# Schematic.net
KiCad netlist of a schematic drawn in EAGLE
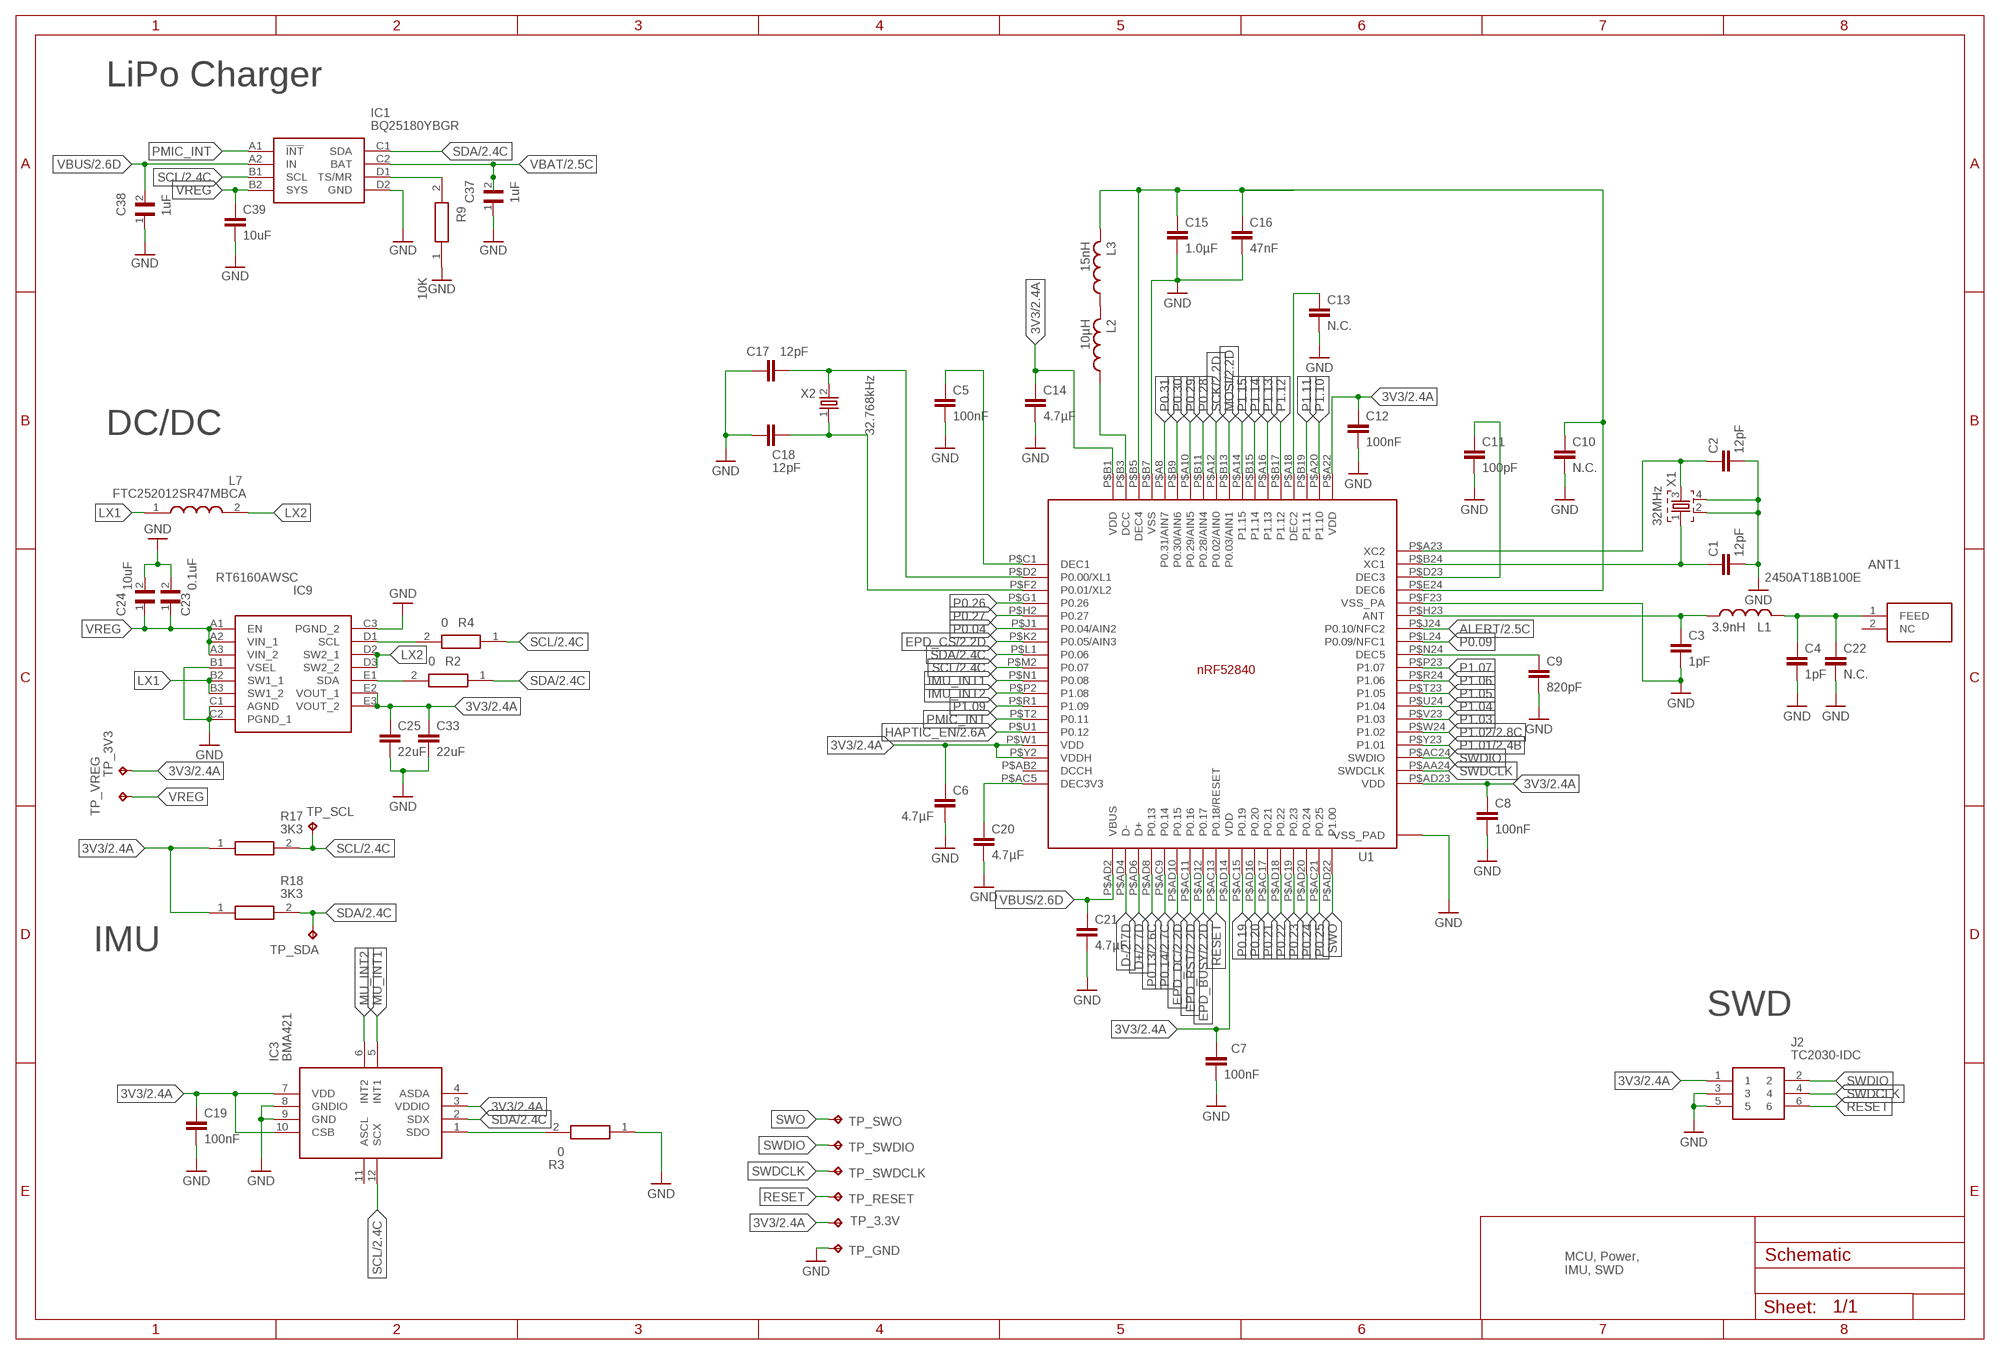
[diagram p0: schematic, sheet 1, part 1 of 2]
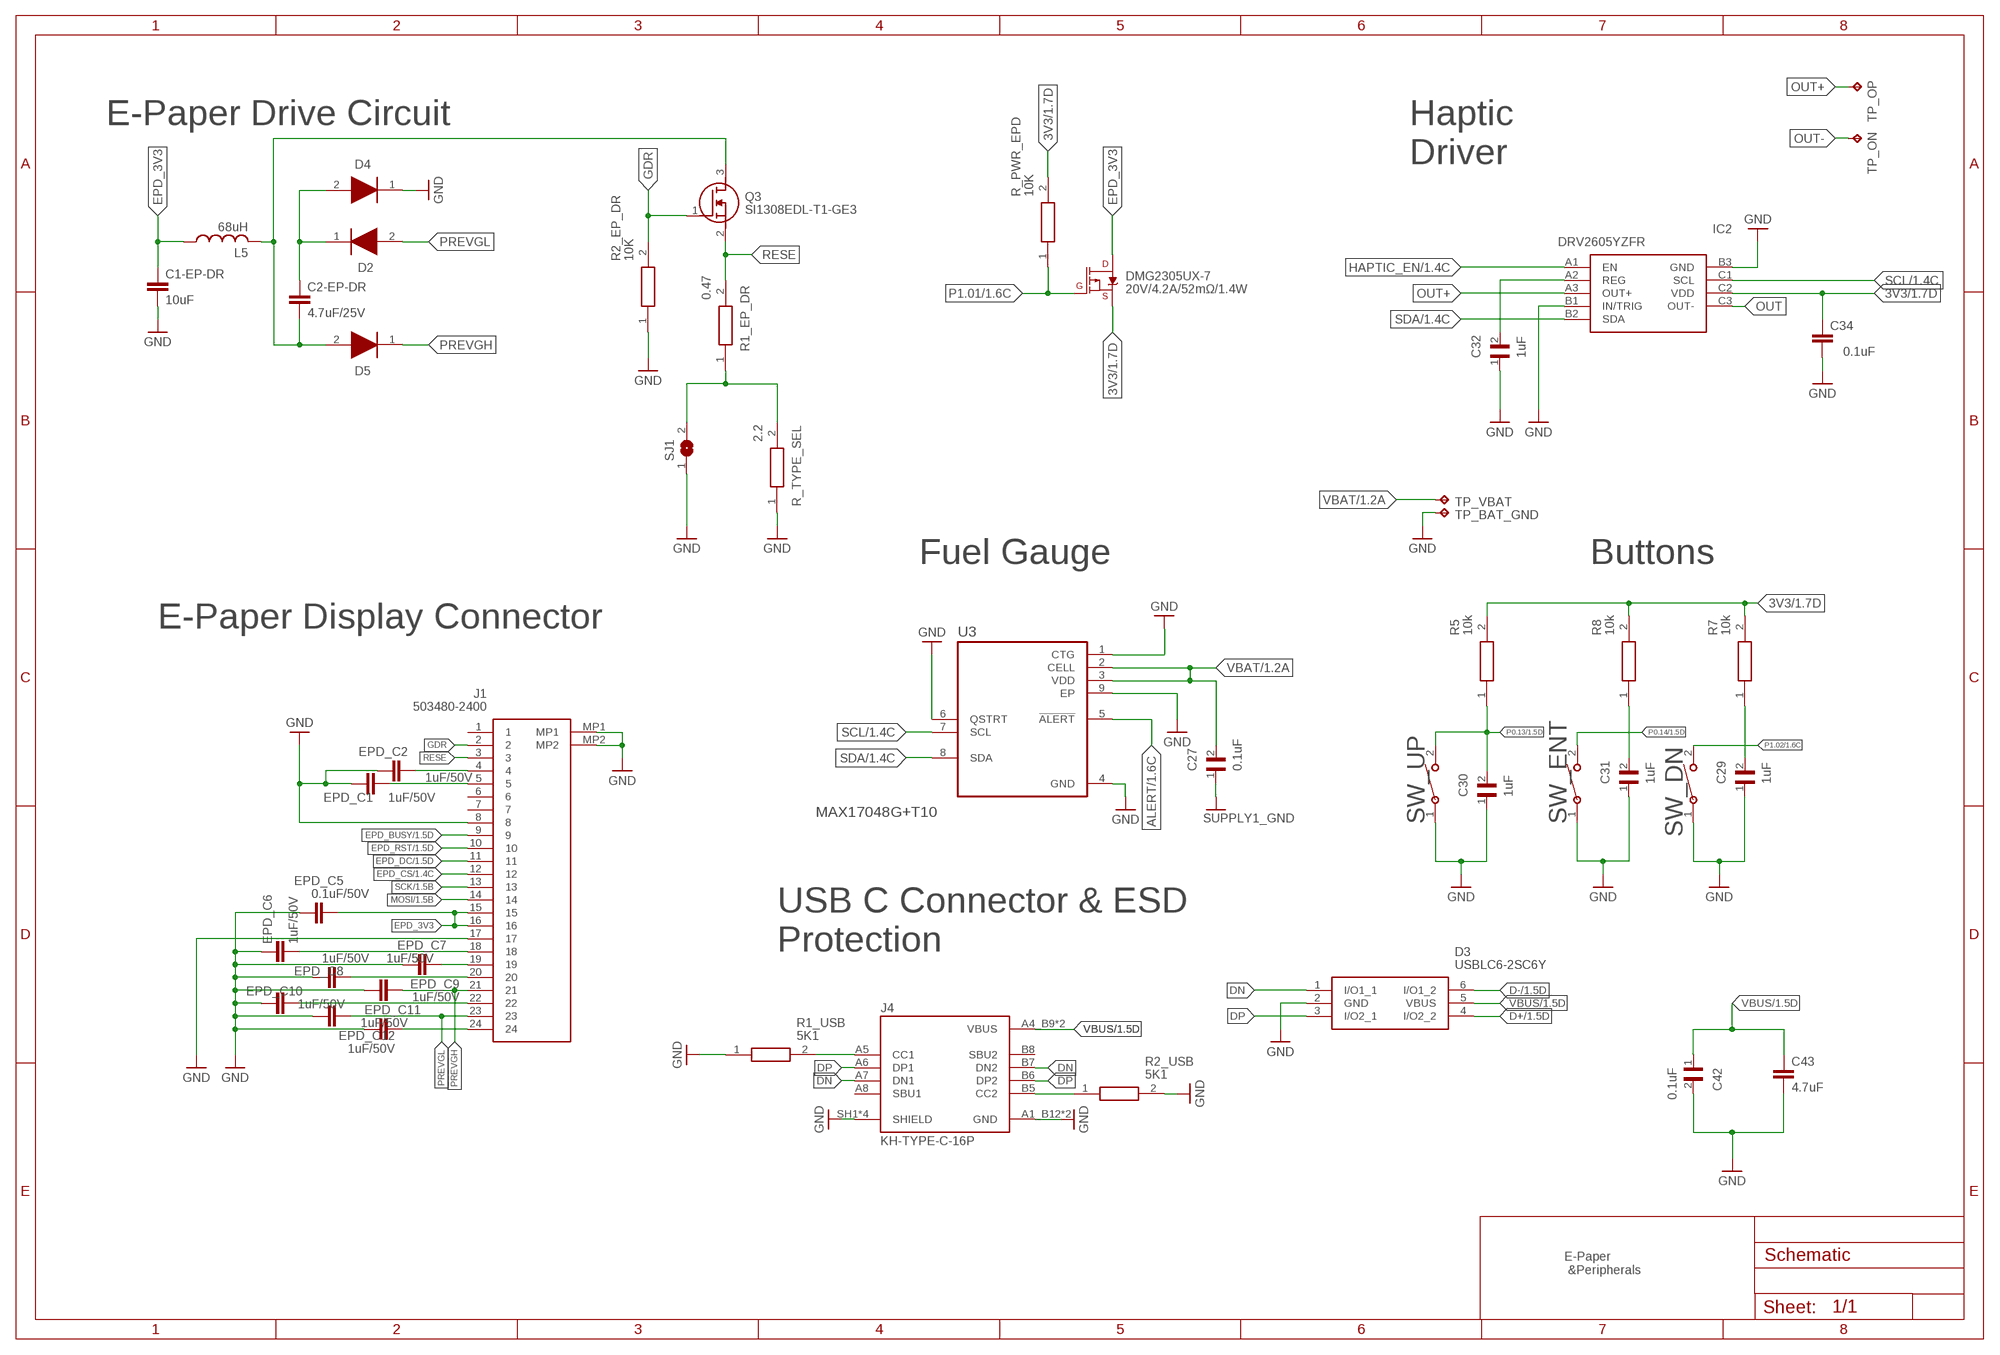
[diagram p1: schematic, sheet 1, part 2 of 2]

(export (version "E")
  (design (tool "Eeschema 10.0.6"))
  (components
    (comp (ref "ANT1")
      (value "2450AT18B100E")
      (footprint "eagle-import:2450AT18B100E_ANTC3216X140N")
      (fields (field (name "MOUSER_PART_NUMBER") "609-2450AT18B100E"))
      (libsource (lib "eagle-import") (part "2450AT18B100E_2450AT18B100E"))
    )
    (comp (ref "C1")
      (value "12pF")
      (footprint "eagle-import:NORDIC_NRF_3_RESC0201_L")
      (libsource (lib "eagle-import") (part "NORDIC_NRF_3_CAPACITOR_0201_L"))
    )
    (comp (ref "C1-EP-DR")
      (value "10uF")
      (footprint "eagle-import:NORDIC_NRF_3_RESC0201_L")
      (libsource (lib "eagle-import") (part "NORDIC_NRF_3_CAPACITOR_0201_L"))
    )
    (comp (ref "C2")
      (value "12pF")
      (footprint "eagle-import:NORDIC_NRF_3_RESC0201_L")
      (libsource (lib "eagle-import") (part "NORDIC_NRF_3_CAPACITOR_0201_L"))
    )
    (comp (ref "C2-EP-DR")
      (value "4.7uF/25V")
      (footprint "eagle-import:NORDIC_NRF_3_RESC0201_L")
      (libsource (lib "eagle-import") (part "NORDIC_NRF_3_CAPACITOR_0201_L"))
    )
    (comp (ref "C3")
      (value "1pF")
      (footprint "eagle-import:NORDIC_NRF_3_RESC0201_L")
      (libsource (lib "eagle-import") (part "NORDIC_NRF_3_CAPACITOR_0201_L"))
    )
    (comp (ref "C4")
      (value "1pF")
      (footprint "eagle-import:NORDIC_NRF_3_RESC0201_L")
      (libsource (lib "eagle-import") (part "NORDIC_NRF_3_CAPACITOR_0201_L"))
    )
    (comp (ref "C5")
      (value "100nF")
      (footprint "eagle-import:NORDIC_NRF_3_RESC0201_L")
      (libsource (lib "eagle-import") (part "NORDIC_NRF_3_CAPACITOR_0201_L"))
    )
    (comp (ref "C6")
      (value "4.7µF")
      (footprint "eagle-import:NORDIC_NRF_3_RESC0201_L")
      (libsource (lib "eagle-import") (part "NORDIC_NRF_3_CAPACITOR_0201_L"))
    )
    (comp (ref "C7")
      (value "100nF")
      (footprint "eagle-import:NORDIC_NRF_3_RESC0201_L")
      (libsource (lib "eagle-import") (part "NORDIC_NRF_3_CAPACITOR_0201_L"))
    )
    (comp (ref "C8")
      (value "100nF")
      (footprint "eagle-import:NORDIC_NRF_3_RESC0201_L")
      (libsource (lib "eagle-import") (part "NORDIC_NRF_3_CAPACITOR_0201_L"))
    )
    (comp (ref "C9")
      (value "820pF")
      (footprint "eagle-import:NORDIC_NRF_3_RESC0201_L")
      (libsource (lib "eagle-import") (part "NORDIC_NRF_3_CAPACITOR_0201_L"))
    )
    (comp (ref "C10")
      (value "N.C.")
      (footprint "eagle-import:NORDIC_NRF_3_RESC0201_L")
      (libsource (lib "eagle-import") (part "NORDIC_NRF_3_CAPACITOR_0201_L"))
    )
    (comp (ref "C11")
      (value "100pF")
      (footprint "eagle-import:NORDIC_NRF_3_RESC0201_L")
      (libsource (lib "eagle-import") (part "NORDIC_NRF_3_CAPACITOR_0201_L"))
    )
    (comp (ref "C12")
      (value "100nF")
      (footprint "eagle-import:NORDIC_NRF_3_RESC0201_L")
      (libsource (lib "eagle-import") (part "NORDIC_NRF_3_CAPACITOR_0201_L"))
    )
    (comp (ref "C13")
      (value "N.C.")
      (footprint "eagle-import:NORDIC_NRF_3_RESC0201_L")
      (libsource (lib "eagle-import") (part "NORDIC_NRF_3_CAPACITOR_0201_L"))
    )
    (comp (ref "C14")
      (value "4.7µF")
      (footprint "eagle-import:PERFECT_0402_0402")
      (libsource (lib "eagle-import") (part "PERFECT_0402_CAP_0402"))
    )
    (comp (ref "C15")
      (value "1.0µF")
      (footprint "eagle-import:NORDIC_NRF_3_RESC0201_L")
      (libsource (lib "eagle-import") (part "NORDIC_NRF_3_CAPACITOR_0201_L"))
    )
    (comp (ref "C16")
      (value "47nF")
      (footprint "eagle-import:NORDIC_NRF_3_RESC0201_L")
      (libsource (lib "eagle-import") (part "NORDIC_NRF_3_CAPACITOR_0201_L"))
    )
    (comp (ref "C17")
      (value "12pF")
      (footprint "eagle-import:NORDIC_NRF_3_RESC0201_L")
      (libsource (lib "eagle-import") (part "NORDIC_NRF_3_CAPACITOR_0201_L"))
    )
    (comp (ref "C18")
      (value "12pF")
      (footprint "eagle-import:NORDIC_NRF_3_RESC0201_L")
      (libsource (lib "eagle-import") (part "NORDIC_NRF_3_CAPACITOR_0201_L"))
    )
    (comp (ref "C19")
      (value "100nF")
      (footprint "eagle-import:NORDIC_NRF_3_RESC0201_L")
      (libsource (lib "eagle-import") (part "NORDIC_NRF_3_CAPACITOR_0201_L"))
    )
    (comp (ref "C20")
      (value "4.7µF")
      (footprint "eagle-import:PERFECT_0402_0402")
      (libsource (lib "eagle-import") (part "PERFECT_0402_CAP_0402"))
    )
    (comp (ref "C21")
      (value "4.7µF")
      (footprint "eagle-import:PERFECT_0402_0402")
      (libsource (lib "eagle-import") (part "PERFECT_0402_CAP_0402"))
    )
    (comp (ref "C22")
      (value "N.C.")
      (footprint "eagle-import:NORDIC_NRF_3_RESC0201_L")
      (libsource (lib "eagle-import") (part "NORDIC_NRF_3_CAPACITOR_0201_L"))
    )
    (comp (ref "C23")
      (value "0.1uF")
      (footprint "eagle-import:GRM011R60J152KE01L_2_CAPC0201X13N")
      (fields (field (name "MF") "Murata") (field (name "MP") "GRM011R60J152KE01L"))
      (libsource (lib "eagle-import") (part "GRM011R60J152KE01L_2_GRM011R60J152KE01L"))
    )
    (comp (ref "C24")
      (value "10uF")
      (footprint "eagle-import:GRM011R60J152KE01L_2_CAPC0201X13N")
      (fields (field (name "MF") "Murata") (field (name "MP") "GRM011R60J152KE01L"))
      (libsource (lib "eagle-import") (part "GRM011R60J152KE01L_2_GRM011R60J152KE01L"))
    )
    (comp (ref "C25")
      (value "22uF")
      (footprint "eagle-import:PERFECT_0402_0402")
      (libsource (lib "eagle-import") (part "PERFECT_0402_CAP_0402"))
    )
    (comp (ref "C27")
      (value "0.1uF")
      (footprint "eagle-import:GRM011R60J152KE01L_2_CAPC0201X13N")
      (fields (field (name "MF") "Murata") (field (name "MP") "GRM011R60J152KE01L"))
      (libsource (lib "eagle-import") (part "GRM011R60J152KE01L_2_GRM011R60J152KE01L"))
    )
    (comp (ref "C29")
      (value "1uF")
      (footprint "eagle-import:GRM011R60J152KE01L_2_CAPC0201X13N")
      (fields (field (name "MF") "Murata") (field (name "MP") "GRM011R60J152KE01L"))
      (libsource (lib "eagle-import") (part "GRM011R60J152KE01L_2_GRM011R60J152KE01L"))
    )
    (comp (ref "C30")
      (value "1uF")
      (footprint "eagle-import:GRM011R60J152KE01L_2_CAPC0201X13N")
      (fields (field (name "MF") "Murata") (field (name "MP") "GRM011R60J152KE01L"))
      (libsource (lib "eagle-import") (part "GRM011R60J152KE01L_2_GRM011R60J152KE01L"))
    )
    (comp (ref "C31")
      (value "1uF")
      (footprint "eagle-import:GRM011R60J152KE01L_2_CAPC0201X13N")
      (fields (field (name "MF") "Murata") (field (name "MP") "GRM011R60J152KE01L"))
      (libsource (lib "eagle-import") (part "GRM011R60J152KE01L_2_GRM011R60J152KE01L"))
    )
    (comp (ref "C32")
      (value "1uF")
      (footprint "eagle-import:GRM011R60J152KE01L_2_CAPC0201X13N")
      (fields (field (name "MF") "Murata") (field (name "MP") "GRM011R60J152KE01L"))
      (libsource (lib "eagle-import") (part "GRM011R60J152KE01L_2_GRM011R60J152KE01L"))
    )
    (comp (ref "C33")
      (value "22uF")
      (footprint "eagle-import:PERFECT_0402_0402")
      (libsource (lib "eagle-import") (part "PERFECT_0402_CAP_0402"))
    )
    (comp (ref "C34")
      (value "0.1uF")
      (footprint "eagle-import:NORDIC_NRF_3_RESC0201_L")
      (libsource (lib "eagle-import") (part "NORDIC_NRF_3_CAPACITOR_0201_L"))
    )
    (comp (ref "C37")
      (value "1uF")
      (footprint "eagle-import:GRM011R60J152KE01L_2_CAPC0201X13N")
      (fields (field (name "MF") "Murata") (field (name "MP") "GRM011R60J152KE01L"))
      (libsource (lib "eagle-import") (part "GRM011R60J152KE01L_2_GRM011R60J152KE01L"))
    )
    (comp (ref "C38")
      (value "1uF")
      (footprint "eagle-import:GRM011R60J152KE01L_2_CAPC0201X13N")
      (fields (field (name "MF") "Murata") (field (name "MP") "GRM011R60J152KE01L"))
      (libsource (lib "eagle-import") (part "GRM011R60J152KE01L_2_GRM011R60J152KE01L"))
    )
    (comp (ref "C39")
      (value "10uF")
      (footprint "eagle-import:NORDIC_NRF_3_RESC0201_L")
      (libsource (lib "eagle-import") (part "NORDIC_NRF_3_CAPACITOR_0201_L"))
    )
    (comp (ref "C42")
      (value "0.1uF")
      (footprint "eagle-import:GRM011R60J152KE01L_2_CAPC0201X13N")
      (fields (field (name "MF") "Murata") (field (name "MP") "GRM011R60J152KE01L"))
      (libsource (lib "eagle-import") (part "GRM011R60J152KE01L_2_GRM011R60J152KE01L"))
    )
    (comp (ref "C43")
      (value "4.7uF")
      (footprint "eagle-import:PERFECT_0402_0402")
      (libsource (lib "eagle-import") (part "PERFECT_0402_CAP_0402"))
    )
    (comp (ref "D2")
      (value "ESP32_C6_LIBRARY_5_MBR0530")
      (footprint "eagle-import:ESP32_C6_LIBRARY_5_SOD3716X135N")
      (fields (field (name "MF") "ON Semiconductor") (field (name "MP") "MBR0530"))
      (libsource (lib "eagle-import") (part "ESP32_C6_LIBRARY_5_MBR0530"))
    )
    (comp (ref "D3")
      (value "USBLC6-2SC6Y")
      (footprint "eagle-import:ESP32_C6_LIBRARY_3_SOT95P280X145-6N")
      (fields (field (name "MF") "STMicroelectronics"))
      (libsource (lib "eagle-import") (part "ESP32_C6_LIBRARY_3_USBLC6-2SC6Y"))
    )
    (comp (ref "D4")
      (value "ESP32_C6_LIBRARY_5_MBR0530")
      (footprint "eagle-import:ESP32_C6_LIBRARY_5_SOD3716X135N")
      (fields (field (name "MF") "ON Semiconductor") (field (name "MP") "MBR0530"))
      (libsource (lib "eagle-import") (part "ESP32_C6_LIBRARY_5_MBR0530"))
    )
    (comp (ref "D5")
      (value "ESP32_C6_LIBRARY_5_MBR0530")
      (footprint "eagle-import:ESP32_C6_LIBRARY_5_SOD3716X135N")
      (fields (field (name "MF") "ON Semiconductor") (field (name "MP") "MBR0530"))
      (libsource (lib "eagle-import") (part "ESP32_C6_LIBRARY_5_MBR0530"))
    )
    (comp (ref "DMG2305UX-7")
      (value "20V/4.2A/52mΩ/1.4W")
      (footprint "eagle-import:ESP32_C6_LIBRARY_4_ESP32_C6_LIBRARY_4_ESP32_C6_LIBRARY_4_ESP32_C6_LIBRARY_4_ESP32_WROVER_SPARKFUN-DISCRETESEMI_SOT23-3")
      (libsource (lib "eagle-import") (part "ESP32_C6_LIBRARY_4_ESP32_WROVER_SPARKFUN-DISCRETESEMI_MOSFET_PCH-DMG2305UX-7"))
    )
    (comp (ref "EPD_C1")
      (value "1uF/50V")
      (footprint "eagle-import:PERFECT_0402_0402")
      (libsource (lib "eagle-import") (part "PERFECT_0402_CAP_0402"))
    )
    (comp (ref "EPD_C2")
      (value "1uF/50V")
      (footprint "eagle-import:PERFECT_0402_0402")
      (libsource (lib "eagle-import") (part "PERFECT_0402_CAP_0402"))
    )
    (comp (ref "EPD_C5")
      (value "0.1uF/50V")
      (footprint "eagle-import:PERFECT_0402_0402")
      (libsource (lib "eagle-import") (part "PERFECT_0402_CAP_0402"))
    )
    (comp (ref "EPD_C6")
      (value "1uF/50V")
      (footprint "eagle-import:PERFECT_0402_0402")
      (libsource (lib "eagle-import") (part "PERFECT_0402_CAP_0402"))
    )
    (comp (ref "EPD_C7")
      (value "1uF/50V")
      (footprint "eagle-import:PERFECT_0402_0402")
      (libsource (lib "eagle-import") (part "PERFECT_0402_CAP_0402"))
    )
    (comp (ref "EPD_C8")
      (value "1uF/50V")
      (footprint "eagle-import:PERFECT_0402_0402")
      (libsource (lib "eagle-import") (part "PERFECT_0402_CAP_0402"))
    )
    (comp (ref "EPD_C9")
      (value "1uF/50V")
      (footprint "eagle-import:PERFECT_0402_0402")
      (libsource (lib "eagle-import") (part "PERFECT_0402_CAP_0402"))
    )
    (comp (ref "EPD_C10")
      (value "1uF/50V")
      (footprint "eagle-import:PERFECT_0402_0402")
      (libsource (lib "eagle-import") (part "PERFECT_0402_CAP_0402"))
    )
    (comp (ref "EPD_C11")
      (value "1uF/50V")
      (footprint "eagle-import:PERFECT_0402_0402")
      (libsource (lib "eagle-import") (part "PERFECT_0402_CAP_0402"))
    )
    (comp (ref "EPD_C12")
      (value "1uF/50V")
      (footprint "eagle-import:PERFECT_0402_0402")
      (libsource (lib "eagle-import") (part "PERFECT_0402_CAP_0402"))
    )
    (comp (ref "IC1")
      (value "BQ25180YBGR")
      (footprint "eagle-import:BQ25180YBGR_BGA8C40P2X4_100X155X50")
      (fields (field (name "MOUSER_PART_NUMBER") "595-BQ25180YBGR"))
      (libsource (lib "eagle-import") (part "BQ25180YBGR_BQ25180YBGR"))
    )
    (comp (ref "IC2")
      (value "DRV2605YZFR")
      (footprint "eagle-import:DRV2605YZFR_BGA9C50P3X3_144X144X62")
      (libsource (lib "eagle-import") (part "DRV2605YZFR_DRV2605YZFR"))
    )
    (comp (ref "IC3")
      (value "BMA421")
      (footprint "eagle-import:BMA423_BMA423")
      (fields (field (name "ARROW_PART_NUMBER") "BMA423") (field (name "MOUSER_PART_NUMBER") "262-BMA423"))
      (libsource (lib "eagle-import") (part "BMA423_BMA423"))
    )
    (comp (ref "IC9")
      (value "RT6160AWSC")
      (footprint "eagle-import:RT6160AWSC_BGA15C40P3X5_140X230X60")
      (fields (field (name "MOUSER_PART_NUMBER") "835-RT6160AWSC"))
      (libsource (lib "eagle-import") (part "RT6160AWSC_RT6160AWSC"))
    )
    (comp (ref "J1")
      (value "503480-2400")
      (footprint "eagle-import:503480-2400_5034802400")
      (fields (field (name "MOUSER_PART_NUMBER") "538-503480-2400"))
      (libsource (lib "eagle-import") (part "503480-2400_503480-2400"))
    )
    (comp (ref "J2")
      (value "TC2030-IDC")
      (footprint "eagle-import:TC2030-IDC_TC2030IDC")
      (libsource (lib "eagle-import") (part "TC2030-IDC_TC2030-IDC"))
    )
    (comp (ref "J4")
      (value "KH-TYPE-C-16P")
      (footprint "eagle-import:KH-TYPE-C-16P_KINGHELM_KH-TYPE-C-16P")
      (fields (field (name "MF") "kinghelm"))
      (libsource (lib "eagle-import") (part "KH-TYPE-C-16P_KH-TYPE-C-16P"))
    )
    (comp (ref "L1")
      (value "3.9nH")
      (footprint "eagle-import:NORDIC_NRF_2_RESC0402_L")
      (libsource (lib "eagle-import") (part "NORDIC_NRF_2_INDUCTOR_0402_L"))
    )
    (comp (ref "L2")
      (value "10µH")
      (footprint "eagle-import:NORDIC_NRF_2_RESC0402_L")
      (libsource (lib "eagle-import") (part "NORDIC_NRF_2_INDUCTOR_0402_L"))
    )
    (comp (ref "L3")
      (value "15nH")
      (footprint "eagle-import:NORDIC_NRF_2_RESC0402_L")
      (libsource (lib "eagle-import") (part "NORDIC_NRF_2_INDUCTOR_0402_L"))
    )
    (comp (ref "L5")
      (value "68uH")
      (footprint "eagle-import:NORDIC_NRF_2_RESC0402_L")
      (libsource (lib "eagle-import") (part "NORDIC_NRF_2_INDUCTOR_0402_L"))
    )
    (comp (ref "L7")
      (value "FTC252012SR47MBCA")
      (footprint "eagle-import:MLP2016SR47MT0S1_INDC2016X100N")
      (libsource (lib "eagle-import") (part "MLP2016SR47MT0S1_FTC252012SR47MBCA"))
    )
    (comp (ref "Q3")
      (value "SI1308EDL-T1-GE3")
      (footprint "eagle-import:ESP32_C6_LIBRARY_6_SOT65P210X110-3N")
      (fields (field (name "MF") "Vishay Siliconix"))
      (libsource (lib "eagle-import") (part "ESP32_C6_LIBRARY_6_SI1308EDL-T1-GE3"))
    )
    (comp (ref "R1_EP_DR")
      (value "0.47")
      (footprint "eagle-import:ERA-1AEB3401C_0201")
      (libsource (lib "eagle-import") (part "ERA-1AEB3401C_CPF0201D7K68C1"))
    )
    (comp (ref "R1_USB")
      (value "5K1")
      (footprint "eagle-import:CPF0201D7K68C1_0201")
      (libsource (lib "eagle-import") (part "CPF0201D7K68C1_CPF0201D7K68C1"))
    )
    (comp (ref "R2")
      (value "0")
      (footprint "eagle-import:CPF0201D7K68C1_0201")
      (libsource (lib "eagle-import") (part "CPF0201D7K68C1_CPF0201D7K68C1"))
    )
    (comp (ref "R2_EP_DR")
      (value "10K")
      (footprint "eagle-import:ERA-1AEB3401C_0201")
      (libsource (lib "eagle-import") (part "ERA-1AEB3401C_CPF0201D7K68C1"))
    )
    (comp (ref "R2_USB")
      (value "5K1")
      (footprint "eagle-import:ERA-1AEB3401C_0201")
      (libsource (lib "eagle-import") (part "ERA-1AEB3401C_CPF0201D7K68C1"))
    )
    (comp (ref "R3")
      (value "0")
      (footprint "eagle-import:ERA-1AEB3401C_0201")
      (libsource (lib "eagle-import") (part "ERA-1AEB3401C_CPF0201D7K68C1"))
    )
    (comp (ref "R4")
      (value "0")
      (footprint "eagle-import:CPF0201D7K68C1_0201")
      (libsource (lib "eagle-import") (part "CPF0201D7K68C1_CPF0201D7K68C1"))
    )
    (comp (ref "R5")
      (value "10k")
      (footprint "eagle-import:CPF0201D7K68C1_0201")
      (libsource (lib "eagle-import") (part "CPF0201D7K68C1_CPF0201D7K68C1"))
    )
    (comp (ref "R7")
      (value "10k")
      (footprint "eagle-import:CPF0201D7K68C1_0201")
      (libsource (lib "eagle-import") (part "CPF0201D7K68C1_CPF0201D7K68C1"))
    )
    (comp (ref "R8")
      (value "10k")
      (footprint "eagle-import:CPF0201D7K68C1_0201")
      (libsource (lib "eagle-import") (part "CPF0201D7K68C1_CPF0201D7K68C1"))
    )
    (comp (ref "R9")
      (value "10K")
      (footprint "eagle-import:ERA-1AEB3401C_0201")
      (libsource (lib "eagle-import") (part "ERA-1AEB3401C_CPF0201D7K68C1"))
    )
    (comp (ref "R17")
      (value "3K3")
      (footprint "eagle-import:CPF0201D7K68C1_0201")
      (libsource (lib "eagle-import") (part "CPF0201D7K68C1_CPF0201D7K68C1"))
    )
    (comp (ref "R18")
      (value "3K3")
      (footprint "eagle-import:CPF0201D7K68C1_0201")
      (libsource (lib "eagle-import") (part "CPF0201D7K68C1_CPF0201D7K68C1"))
    )
    (comp (ref "R_PWR_EPD")
      (value "10K")
      (footprint "eagle-import:CPF0201D7K68C1_0201")
      (libsource (lib "eagle-import") (part "CPF0201D7K68C1_CPF0201D7K68C1"))
    )
    (comp (ref "R_TYPE_SEL")
      (value "2.2")
      (footprint "eagle-import:ERA-1AEB3401C_0201")
      (libsource (lib "eagle-import") (part "ERA-1AEB3401C_CPF0201D7K68C1"))
    )
    (comp (ref "SJ1")
      (value "ESP32_C6_LIBRARY_7_JUMPER_SJ")
      (footprint "eagle-import:ESP32_C6_LIBRARY_7_JUMPER_SJ")
      (libsource (lib "eagle-import") (part "ESP32_C6_LIBRARY_7_JUMPER_SJ"))
    )
    (comp (ref "SW_DN")
      (value "2025-10-22_07-23-44_LIBRARY_EVP-AKE31ASW_EVP-AKE31A_PAN")
      (footprint "eagle-import:2025-10-22_07-23-44_LIBRARY_SW_EVP-AKE31A_PAN")
      (fields
        (field (name "MANUFACTURER_PART_NUMBER") "EVP-AKE31A")
        (field (name "COPYRIGHT") "Copyright (C) 2025 Ultra Librarian. All rights reserved.")
      )
      (libsource (lib "eagle-import") (part "2025-10-22_07-23-44_LIBRARY_EVP-AKE31ASW_EVP-AKE31A_PAN"))
    )
    (comp (ref "SW_ENT")
      (value "2025-10-22_07-23-44_LIBRARY_EVP-AKE31ASW_EVP-AKE31A_PAN")
      (footprint "eagle-import:2025-10-22_07-23-44_LIBRARY_SW_EVP-AKE31A_PAN")
      (fields
        (field (name "MANUFACTURER_PART_NUMBER") "EVP-AKE31A")
        (field (name "COPYRIGHT") "Copyright (C) 2025 Ultra Librarian. All rights reserved.")
      )
      (libsource (lib "eagle-import") (part "2025-10-22_07-23-44_LIBRARY_EVP-AKE31ASW_EVP-AKE31A_PAN"))
    )
    (comp (ref "SW_UP")
      (value "2025-10-22_07-23-44_LIBRARY_EVP-AKE31ASW_EVP-AKE31A_PAN")
      (footprint "eagle-import:2025-10-22_07-23-44_LIBRARY_SW_EVP-AKE31A_PAN")
      (fields
        (field (name "MANUFACTURER_PART_NUMBER") "EVP-AKE31A")
        (field (name "COPYRIGHT") "Copyright (C) 2025 Ultra Librarian. All rights reserved.")
      )
      (libsource (lib "eagle-import") (part "2025-10-22_07-23-44_LIBRARY_EVP-AKE31ASW_EVP-AKE31A_PAN"))
    )
    (comp (ref "TP_3.3V")
      (value "HECTOR_WATCH_1_TPTP20R")
      (footprint "eagle-import:HECTOR_WATCH_1_TP20R")
      (libsource (lib "eagle-import") (part "HECTOR_WATCH_1_TPTP20R"))
    )
    (comp (ref "TP_3V3")
      (value "HECTOR_WATCH_1_TPTP20R")
      (footprint "eagle-import:HECTOR_WATCH_1_TP20R")
      (libsource (lib "eagle-import") (part "HECTOR_WATCH_1_TPTP20R"))
    )
    (comp (ref "TP_BAT_GND")
      (value "HECTOR_WATCH_1_TPTP20R")
      (footprint "eagle-import:HECTOR_WATCH_1_TP20R")
      (libsource (lib "eagle-import") (part "HECTOR_WATCH_1_TPTP20R"))
    )
    (comp (ref "TP_GND")
      (value "HECTOR_WATCH_1_TPTP20R")
      (footprint "eagle-import:HECTOR_WATCH_1_TP20R")
      (libsource (lib "eagle-import") (part "HECTOR_WATCH_1_TPTP20R"))
    )
    (comp (ref "TP_ON")
      (value "HECTOR_WATCH_1_TPTP20R")
      (footprint "eagle-import:HECTOR_WATCH_1_TP20R")
      (libsource (lib "eagle-import") (part "HECTOR_WATCH_1_TPTP20R"))
    )
    (comp (ref "TP_OP")
      (value "HECTOR_WATCH_1_TPTP20R")
      (footprint "eagle-import:HECTOR_WATCH_1_TP20R")
      (libsource (lib "eagle-import") (part "HECTOR_WATCH_1_TPTP20R"))
    )
    (comp (ref "TP_RESET")
      (value "HECTOR_WATCH_1_TPTP20R")
      (footprint "eagle-import:HECTOR_WATCH_1_TP20R")
      (libsource (lib "eagle-import") (part "HECTOR_WATCH_1_TPTP20R"))
    )
    (comp (ref "TP_SCL")
      (value "HECTOR_WATCH_1_TPTP20R")
      (footprint "eagle-import:HECTOR_WATCH_1_TP20R")
      (libsource (lib "eagle-import") (part "HECTOR_WATCH_1_TPTP20R"))
    )
    (comp (ref "TP_SDA")
      (value "HECTOR_WATCH_1_TPTP20R")
      (footprint "eagle-import:HECTOR_WATCH_1_TP20R")
      (libsource (lib "eagle-import") (part "HECTOR_WATCH_1_TPTP20R"))
    )
    (comp (ref "TP_SWDCLK")
      (value "HECTOR_WATCH_1_TPTP20R")
      (footprint "eagle-import:HECTOR_WATCH_1_TP20R")
      (libsource (lib "eagle-import") (part "HECTOR_WATCH_1_TPTP20R"))
    )
    (comp (ref "TP_SWDIO")
      (value "HECTOR_WATCH_1_TPTP20R")
      (footprint "eagle-import:HECTOR_WATCH_1_TP20R")
      (libsource (lib "eagle-import") (part "HECTOR_WATCH_1_TPTP20R"))
    )
    (comp (ref "TP_SWO")
      (value "HECTOR_WATCH_1_TPTP20R")
      (footprint "eagle-import:HECTOR_WATCH_1_TP20R")
      (libsource (lib "eagle-import") (part "HECTOR_WATCH_1_TPTP20R"))
    )
    (comp (ref "TP_VBAT")
      (value "HECTOR_WATCH_1_TPTP20R")
      (footprint "eagle-import:HECTOR_WATCH_1_TP20R")
      (libsource (lib "eagle-import") (part "HECTOR_WATCH_1_TPTP20R"))
    )
    (comp (ref "TP_VREG")
      (value "HECTOR_WATCH_1_TPTP20R")
      (footprint "eagle-import:HECTOR_WATCH_1_TP20R")
      (libsource (lib "eagle-import") (part "HECTOR_WATCH_1_TPTP20R"))
    )
    (comp (ref "U1")
      (value "NRF52840_QF")
      (footprint "eagle-import:NORDIC_NRF_4_AQFN50P700X700X85_HS-74N")
      (libsource (lib "eagle-import") (part "NORDIC_NRF_4_NRF52840_QF"))
    )
    (comp (ref "U3")
      (value "MAX17048G+T10")
      (footprint "eagle-import:ESP32_C6_LIBRARY_SON50P200X200X80-9N")
      (fields (field (name "MF") "Analog Devices"))
      (libsource (lib "eagle-import") (part "ESP32_C6_LIBRARY_MAX17048G+T10"))
    )
    (comp (ref "X1")
      (value "32MHz")
      (footprint "eagle-import:NORDIC_NRF_BT-XTAL_2016_N")
      (libsource (lib "eagle-import") (part "NORDIC_NRF_XTAL_32MHZ"))
    )
    (comp (ref "X2")
      (value "32.768kHz")
      (footprint "eagle-import:NORDIC_NRF_1_XTAL_3215_N")
      (libsource (lib "eagle-import") (part "NORDIC_NRF_1_XTAL_32KHZ"))
    )
  )
  (nets
    (net (code "1") (name "3V3{slash}1.7D") (class "Default")
      (node (ref "C34") (pin "1") (pinfunction "1_1") (pintype "passive"))
      (node (ref "DMG2305UX-7") (pin "2") (pinfunction "S_2") (pintype "bidirectional"))
      (node (ref "IC2") (pin "C2") (pinfunction "VDD_C2") (pintype "bidirectional"))
      (node (ref "R5") (pin "2") (pinfunction "2_2") (pintype "bidirectional"))
      (node (ref "R7") (pin "2") (pinfunction "2_2") (pintype "bidirectional"))
      (node (ref "R8") (pin "2") (pinfunction "2_2") (pintype "bidirectional"))
      (node (ref "R_PWR_EPD") (pin "2") (pinfunction "2_2") (pintype "bidirectional"))
    )
    (net (code "2") (name "3V3{slash}2.4A") (class "Default")
      (node (ref "C12") (pin "1") (pinfunction "1_1") (pintype "passive"))
      (node (ref "C14") (pin "1") (pinfunction "1_1") (pintype "passive"))
      (node (ref "C19") (pin "1") (pinfunction "1_1") (pintype "passive"))
      (node (ref "C25") (pin "1") (pinfunction "1_1") (pintype "passive"))
      (node (ref "C33") (pin "1") (pinfunction "1_1") (pintype "passive"))
      (node (ref "C6") (pin "1") (pinfunction "1_1") (pintype "passive"))
      (node (ref "C7") (pin "1") (pinfunction "1_1") (pintype "passive"))
      (node (ref "C8") (pin "1") (pinfunction "1_1") (pintype "passive"))
      (node (ref "IC3") (pin "10") (pinfunction "CSB_10") (pintype "bidirectional"))
      (node (ref "IC3") (pin "3") (pinfunction "VDDIO_3") (pintype "bidirectional"))
      (node (ref "IC3") (pin "7") (pinfunction "VDD_7") (pintype "bidirectional"))
      (node (ref "IC9") (pin "E2") (pinfunction "VOUT_1_E2") (pintype "bidirectional"))
      (node (ref "IC9") (pin "E3") (pinfunction "VOUT_2_E3") (pintype "bidirectional"))
      (node (ref "J2") (pin "1") (pinfunction "1_1") (pintype "bidirectional"))
      (node (ref "R17") (pin "1") (pinfunction "1_1") (pintype "bidirectional"))
      (node (ref "R18") (pin "1") (pinfunction "1_1") (pintype "bidirectional"))
      (node (ref "TP_3.3V") (pin "TP") (pinfunction "TP_TP") (pintype "input"))
      (node (ref "TP_3V3") (pin "TP") (pinfunction "TP_TP") (pintype "input"))
      (node (ref "U1") (pin "P$A22") (pinfunction "VDD_P$A22") (pintype "power_in"))
      (node (ref "U1") (pin "P$AD14") (pinfunction "VDD_P$AD14") (pintype "power_in"))
      (node (ref "U1") (pin "P$AD23") (pinfunction "VDD_P$AD23") (pintype "power_in"))
      (node (ref "U1") (pin "P$B1") (pinfunction "VDD_P$B1") (pintype "power_in"))
      (node (ref "U1") (pin "P$W1") (pinfunction "VDD_P$W1") (pintype "power_in"))
      (node (ref "U1") (pin "P$Y2") (pinfunction "VDDH_P$Y2") (pintype "power_in"))
    )
    (net (code "3") (name "ALERT{slash}1.6C") (class "Default")
      (node (ref "U3") (pin "5") (pinfunction "~{ALERT}_5") (pintype "output"))
    )
    (net (code "4") (name "ALERT{slash}2.5C") (class "Default")
      (node (ref "U1") (pin "P$J24") (pinfunction "P0.10/NFC2_P$J24") (pintype "bidirectional"))
    )
    (net (code "5") (name "D+{slash}1.5D") (class "Default")
      (node (ref "D3") (pin "4") (pinfunction "I/O2_2_4") (pintype "bidirectional"))
    )
    (net (code "6") (name "D+{slash}2.7D") (class "Default")
      (node (ref "U1") (pin "P$AD6") (pinfunction "D+_P$AD6") (pintype "bidirectional"))
    )
    (net (code "7") (name "D-{slash}1.5D") (class "Default")
      (node (ref "D3") (pin "6") (pinfunction "I/O1_2_6") (pintype "bidirectional"))
    )
    (net (code "8") (name "D-{slash}2.7D") (class "Default")
      (node (ref "U1") (pin "P$AD4") (pinfunction "D-_P$AD4") (pintype "bidirectional"))
    )
    (net (code "9") (name "DN") (class "Default")
      (node (ref "D3") (pin "1") (pinfunction "I/O1_1_1") (pintype "bidirectional"))
      (node (ref "J4") (pin "A7") (pinfunction "DN1_A7") (pintype "bidirectional"))
      (node (ref "J4") (pin "B7") (pinfunction "DN2_B7") (pintype "bidirectional"))
    )
    (net (code "10") (name "DP") (class "Default")
      (node (ref "D3") (pin "3") (pinfunction "I/O2_1_3") (pintype "bidirectional"))
      (node (ref "J4") (pin "A6") (pinfunction "DP1_A6") (pintype "bidirectional"))
      (node (ref "J4") (pin "B6") (pinfunction "DP2_B6") (pintype "bidirectional"))
    )
    (net (code "11") (name "EPD_3V3") (class "Default")
      (node (ref "C1-EP-DR") (pin "1") (pinfunction "1_1") (pintype "passive"))
      (node (ref "DMG2305UX-7") (pin "3") (pinfunction "D_3") (pintype "bidirectional"))
      (node (ref "EPD_C5") (pin "2") (pinfunction "2_2") (pintype "passive"))
      (node (ref "J1") (pin "15") (pinfunction "15_15") (pintype "bidirectional"))
      (node (ref "J1") (pin "16") (pinfunction "16_16") (pintype "bidirectional"))
      (node (ref "L5") (pin "1") (pinfunction "1_1") (pintype "passive"))
    )
    (net (code "12") (name "EPD_BUSY{slash}1.5D") (class "Default")
      (node (ref "J1") (pin "9") (pinfunction "9_9") (pintype "bidirectional"))
    )
    (net (code "13") (name "EPD_BUSY{slash}2.2D") (class "Default")
      (node (ref "U1") (pin "P$AD12") (pinfunction "P0.17_P$AD12") (pintype "bidirectional"))
    )
    (net (code "14") (name "EPD_CS{slash}1.4C") (class "Default")
      (node (ref "J1") (pin "12") (pinfunction "12_12") (pintype "bidirectional"))
    )
    (net (code "15") (name "EPD_CS{slash}2.2D") (class "Default")
      (node (ref "U1") (pin "P$K2") (pinfunction "P0.05/AIN3_P$K2") (pintype "bidirectional"))
    )
    (net (code "16") (name "EPD_DC{slash}1.5D") (class "Default")
      (node (ref "J1") (pin "11") (pinfunction "11_11") (pintype "bidirectional"))
    )
    (net (code "17") (name "EPD_DC{slash}2.2D") (class "Default")
      (node (ref "U1") (pin "P$AD10") (pinfunction "P0.15_P$AD10") (pintype "bidirectional"))
    )
    (net (code "18") (name "EPD_RST{slash}1.5D") (class "Default")
      (node (ref "J1") (pin "10") (pinfunction "10_10") (pintype "bidirectional"))
    )
    (net (code "19") (name "EPD_RST{slash}2.2D") (class "Default")
      (node (ref "U1") (pin "P$AC11") (pinfunction "P0.16_P$AC11") (pintype "bidirectional"))
    )
    (net (code "20") (name "GDR") (class "Default")
      (node (ref "J1") (pin "2") (pinfunction "2_2") (pintype "bidirectional"))
      (node (ref "Q3") (pin "1") (pinfunction "G_1") (pintype "bidirectional"))
      (node (ref "R2_EP_DR") (pin "2") (pinfunction "2_2") (pintype "bidirectional"))
    )
    (net (code "21") (name "GND") (class "Default")
      (node (ref "C1") (pin "2") (pinfunction "2_2") (pintype "passive"))
      (node (ref "C1-EP-DR") (pin "2") (pinfunction "2_2") (pintype "passive"))
      (node (ref "C10") (pin "2") (pinfunction "2_2") (pintype "passive"))
      (node (ref "C11") (pin "2") (pinfunction "2_2") (pintype "passive"))
      (node (ref "C12") (pin "2") (pinfunction "2_2") (pintype "passive"))
      (node (ref "C13") (pin "2") (pinfunction "2_2") (pintype "passive"))
      (node (ref "C14") (pin "2") (pinfunction "2_2") (pintype "passive"))
      (node (ref "C15") (pin "2") (pinfunction "2_2") (pintype "passive"))
      (node (ref "C16") (pin "2") (pinfunction "2_2") (pintype "passive"))
      (node (ref "C17") (pin "1") (pinfunction "1_1") (pintype "passive"))
      (node (ref "C18") (pin "2") (pinfunction "2_2") (pintype "passive"))
      (node (ref "C19") (pin "2") (pinfunction "2_2") (pintype "passive"))
      (node (ref "C2") (pin "2") (pinfunction "2_2") (pintype "passive"))
      (node (ref "C20") (pin "2") (pinfunction "2_2") (pintype "passive"))
      (node (ref "C21") (pin "2") (pinfunction "2_2") (pintype "passive"))
      (node (ref "C22") (pin "2") (pinfunction "2_2") (pintype "passive"))
      (node (ref "C23") (pin "2") (pinfunction "2_2") (pintype "passive"))
      (node (ref "C24") (pin "2") (pinfunction "2_2") (pintype "passive"))
      (node (ref "C25") (pin "2") (pinfunction "2_2") (pintype "passive"))
      (node (ref "C27") (pin "1") (pinfunction "1_1") (pintype "passive"))
      (node (ref "C29") (pin "1") (pinfunction "1_1") (pintype "passive"))
      (node (ref "C3") (pin "2") (pinfunction "2_2") (pintype "passive"))
      (node (ref "C30") (pin "1") (pinfunction "1_1") (pintype "passive"))
      (node (ref "C31") (pin "1") (pinfunction "1_1") (pintype "passive"))
      (node (ref "C32") (pin "1") (pinfunction "1_1") (pintype "passive"))
      (node (ref "C33") (pin "2") (pinfunction "2_2") (pintype "passive"))
      (node (ref "C34") (pin "2") (pinfunction "2_2") (pintype "passive"))
      (node (ref "C37") (pin "1") (pinfunction "1_1") (pintype "passive"))
      (node (ref "C38") (pin "1") (pinfunction "1_1") (pintype "passive"))
      (node (ref "C39") (pin "2") (pinfunction "2_2") (pintype "passive"))
      (node (ref "C4") (pin "2") (pinfunction "2_2") (pintype "passive"))
      (node (ref "C42") (pin "2") (pinfunction "2_2") (pintype "passive"))
      (node (ref "C43") (pin "2") (pinfunction "2_2") (pintype "passive"))
      (node (ref "C5") (pin "2") (pinfunction "2_2") (pintype "passive"))
      (node (ref "C6") (pin "2") (pinfunction "2_2") (pintype "passive"))
      (node (ref "C7") (pin "2") (pinfunction "2_2") (pintype "passive"))
      (node (ref "C8") (pin "2") (pinfunction "2_2") (pintype "passive"))
      (node (ref "C9") (pin "2") (pinfunction "2_2") (pintype "passive"))
      (node (ref "D3") (pin "2") (pinfunction "GND_2") (pintype "bidirectional"))
      (node (ref "D4") (pin "1") (pinfunction "K_1") (pintype "bidirectional"))
      (node (ref "EPD_C1") (pin "1") (pinfunction "1_1") (pintype "passive"))
      (node (ref "EPD_C10") (pin "1") (pinfunction "1_1") (pintype "passive"))
      (node (ref "EPD_C11") (pin "1") (pinfunction "1_1") (pintype "passive"))
      (node (ref "EPD_C12") (pin "1") (pinfunction "1_1") (pintype "passive"))
      (node (ref "EPD_C2") (pin "1") (pinfunction "1_1") (pintype "passive"))
      (node (ref "EPD_C5") (pin "1") (pinfunction "1_1") (pintype "passive"))
      (node (ref "EPD_C6") (pin "1") (pinfunction "1_1") (pintype "passive"))
      (node (ref "EPD_C7") (pin "1") (pinfunction "1_1") (pintype "passive"))
      (node (ref "EPD_C8") (pin "1") (pinfunction "1_1") (pintype "passive"))
      (node (ref "EPD_C9") (pin "1") (pinfunction "1_1") (pintype "passive"))
      (node (ref "IC1") (pin "D2") (pinfunction "GND_D2") (pintype "bidirectional"))
      (node (ref "IC2") (pin "B1") (pinfunction "IN/TRIG_B1") (pintype "bidirectional"))
      (node (ref "IC2") (pin "B3") (pinfunction "GND_B3") (pintype "bidirectional"))
      (node (ref "IC3") (pin "8") (pinfunction "GNDIO_8") (pintype "bidirectional"))
      (node (ref "IC3") (pin "9") (pinfunction "GND_9") (pintype "bidirectional"))
      (node (ref "IC9") (pin "B1") (pinfunction "VSEL_B1") (pintype "bidirectional"))
      (node (ref "IC9") (pin "C1") (pinfunction "AGND_C1") (pintype "bidirectional"))
      (node (ref "IC9") (pin "C2") (pinfunction "PGND_1_C2") (pintype "bidirectional"))
      (node (ref "IC9") (pin "C3") (pinfunction "PGND_2_C3") (pintype "bidirectional"))
      (node (ref "J1") (pin "17") (pinfunction "17_17") (pintype "bidirectional"))
      (node (ref "J1") (pin "8") (pinfunction "8_8") (pintype "bidirectional"))
      (node (ref "J1") (pin "MP1") (pinfunction "MP1_MP1") (pintype "bidirectional"))
      (node (ref "J1") (pin "MP2") (pinfunction "MP2_MP2") (pintype "bidirectional"))
      (node (ref "J2") (pin "3") (pinfunction "3_3") (pintype "bidirectional"))
      (node (ref "J2") (pin "5") (pinfunction "5_5") (pintype "bidirectional"))
      (node (ref "J4") (pin "A12_B1") (pinfunction "GND_A12_B1") (pintype "power_in"))
      (node (ref "J4") (pin "A1_B12") (pinfunction "GND_A1_B12") (pintype "power_in"))
      (node (ref "J4") (pin "SH1") (pinfunction "SHIELD_SH1") (pintype "passive"))
      (node (ref "J4") (pin "SH2") (pinfunction "SHIELD_SH2") (pintype "passive"))
      (node (ref "J4") (pin "SH3") (pinfunction "SHIELD_SH3") (pintype "passive"))
      (node (ref "J4") (pin "SH4") (pinfunction "SHIELD_SH4") (pintype "passive"))
      (node (ref "R1_USB") (pin "1") (pinfunction "1_1") (pintype "bidirectional"))
      (node (ref "R2_EP_DR") (pin "1") (pinfunction "1_1") (pintype "bidirectional"))
      (node (ref "R2_USB") (pin "2") (pinfunction "2_2") (pintype "bidirectional"))
      (node (ref "R3") (pin "1") (pinfunction "1_1") (pintype "bidirectional"))
      (node (ref "R9") (pin "1") (pinfunction "1_1") (pintype "bidirectional"))
      (node (ref "R_TYPE_SEL") (pin "1") (pinfunction "1_1") (pintype "bidirectional"))
      (node (ref "SJ1") (pin "1") (pinfunction "1_1") (pintype "passive"))
      (node (ref "SW_DN") (pin "1") (pinfunction "1_1") (pintype "passive"))
      (node (ref "SW_ENT") (pin "1") (pinfunction "1_1") (pintype "passive"))
      (node (ref "SW_UP") (pin "1") (pinfunction "1_1") (pintype "passive"))
      (node (ref "TP_BAT_GND") (pin "TP") (pinfunction "TP_TP") (pintype "input"))
      (node (ref "TP_GND") (pin "TP") (pinfunction "TP_TP") (pintype "input"))
      (node (ref "U1") (pin "P$74") (pinfunction "VSS_PAD_P$74") (pintype "bidirectional"))
      (node (ref "U1") (pin "P$75") (pinfunction "VSS_PAD_P$75") (pintype "bidirectional"))
      (node (ref "U1") (pin "P$76") (pinfunction "VSS_PAD_P$76") (pintype "bidirectional"))
      (node (ref "U1") (pin "P$77") (pinfunction "VSS_PAD_P$77") (pintype "bidirectional"))
      (node (ref "U1") (pin "P$78") (pinfunction "VSS_PAD_P$78") (pintype "bidirectional"))
      (node (ref "U1") (pin "P$79") (pinfunction "VSS_PAD_P$79") (pintype "bidirectional"))
      (node (ref "U1") (pin "P$80") (pinfunction "VSS_PAD_P$80") (pintype "bidirectional"))
      (node (ref "U1") (pin "P$81") (pinfunction "VSS_PAD_P$81") (pintype "bidirectional"))
      (node (ref "U1") (pin "P$82") (pinfunction "VSS_PAD_P$82") (pintype "bidirectional"))
      (node (ref "U1") (pin "P$83") (pinfunction "VSS_PAD_P$83") (pintype "bidirectional"))
      (node (ref "U1") (pin "P$84") (pinfunction "VSS_PAD_P$84") (pintype "bidirectional"))
      (node (ref "U1") (pin "P$85") (pinfunction "VSS_PAD_P$85") (pintype "bidirectional"))
      (node (ref "U1") (pin "P$86") (pinfunction "VSS_PAD_P$86") (pintype "bidirectional"))
      (node (ref "U1") (pin "P$87") (pinfunction "VSS_PAD_P$87") (pintype "bidirectional"))
      (node (ref "U1") (pin "P$88") (pinfunction "VSS_PAD_P$88") (pintype "bidirectional"))
      (node (ref "U1") (pin "P$89") (pinfunction "VSS_PAD_P$89") (pintype "bidirectional"))
      (node (ref "U1") (pin "P$90") (pinfunction "VSS_PAD_P$90") (pintype "bidirectional"))
      (node (ref "U1") (pin "P$B7") (pinfunction "VSS_P$B7") (pintype "power_in"))
      (node (ref "U1") (pin "P$F23") (pinfunction "VSS_PA_P$F23") (pintype "bidirectional"))
      (node (ref "U3") (pin "1") (pinfunction "CTG_1") (pintype "power_in"))
      (node (ref "U3") (pin "4") (pinfunction "GND_4") (pintype "power_in"))
      (node (ref "U3") (pin "6") (pinfunction "QSTRT_6") (pintype "input"))
      (node (ref "U3") (pin "9") (pinfunction "EP_9") (pintype "power_in"))
      (node (ref "X1") (pin "2") (pinfunction "2_2") (pintype "passive"))
      (node (ref "X1") (pin "4") (pinfunction "4_4") (pintype "passive"))
    )
    (net (code "22") (name "HAPTIC_EN{slash}1.4C") (class "Default")
      (node (ref "IC2") (pin "A1") (pinfunction "EN_A1") (pintype "bidirectional"))
    )
    (net (code "23") (name "HAPTIC_EN{slash}2.6A") (class "Default")
      (node (ref "U1") (pin "P$U1") (pinfunction "P0.12_P$U1") (pintype "bidirectional"))
    )
    (net (code "24") (name "IMU_INT1") (class "Default")
      (node (ref "U1") (pin "P$N1") (pinfunction "P0.08_P$N1") (pintype "bidirectional"))
    )
    (net (code "25") (name "IMU_INT2") (class "Default")
      (node (ref "U1") (pin "P$P2") (pinfunction "P1.08_P$P2") (pintype "bidirectional"))
    )
    (net (code "26") (name "LX1") (class "Default")
      (node (ref "IC9") (pin "B2") (pinfunction "SW1_1_B2") (pintype "bidirectional"))
      (node (ref "IC9") (pin "B3") (pinfunction "SW1_2_B3") (pintype "bidirectional"))
      (node (ref "L7") (pin "1") (pinfunction "1_1") (pintype "bidirectional"))
    )
    (net (code "27") (name "LX2") (class "Default")
      (node (ref "IC9") (pin "D2") (pinfunction "SW2_1_D2") (pintype "bidirectional"))
      (node (ref "IC9") (pin "D3") (pinfunction "SW2_2_D3") (pintype "bidirectional"))
      (node (ref "L7") (pin "2") (pinfunction "2_2") (pintype "bidirectional"))
    )
    (net (code "28") (name "MOSI{slash}1.5B") (class "Default")
      (node (ref "J1") (pin "14") (pinfunction "14_14") (pintype "bidirectional"))
    )
    (net (code "29") (name "MOSI{slash}2.2D") (class "Default")
      (node (ref "U1") (pin "P$B13") (pinfunction "P0.03/AIN1_P$B13") (pintype "bidirectional"))
    )
    (net (code "30") (name "MU_INT1") (class "Default")
      (node (ref "IC3") (pin "5") (pinfunction "INT1_5") (pintype "bidirectional"))
    )
    (net (code "31") (name "MU_INT2") (class "Default")
      (node (ref "IC3") (pin "6") (pinfunction "INT2_6") (pintype "bidirectional"))
    )
    (net (code "32") (name "Net-(ANT1-FEED)") (class "Default")
      (node (ref "ANT1") (pin "1") (pinfunction "FEED_1") (pintype "input"))
      (node (ref "C22") (pin "1") (pinfunction "1_1") (pintype "passive"))
      (node (ref "C4") (pin "1") (pinfunction "1_1") (pintype "passive"))
      (node (ref "L1") (pin "2") (pinfunction "2_2") (pintype "passive"))
    )
    (net (code "33") (name "Net-(C29-Pad2)") (class "Default")
      (node (ref "C29") (pin "2") (pinfunction "2_2") (pintype "passive"))
      (node (ref "R7") (pin "1") (pinfunction "1_1") (pintype "bidirectional"))
    )
    (net (code "34") (name "Net-(C31-Pad2)") (class "Default")
      (node (ref "C31") (pin "2") (pinfunction "2_2") (pintype "passive"))
      (node (ref "R8") (pin "1") (pinfunction "1_1") (pintype "bidirectional"))
    )
    (net (code "35") (name "Net-(D2-K)") (class "Default")
      (node (ref "C2-EP-DR") (pin "1") (pinfunction "1_1") (pintype "passive"))
      (node (ref "D2") (pin "1") (pinfunction "K_1") (pintype "bidirectional"))
      (node (ref "D4") (pin "2") (pinfunction "A_2") (pintype "bidirectional"))
    )
    (net (code "36") (name "Net-(D5-A)") (class "Default")
      (node (ref "C2-EP-DR") (pin "2") (pinfunction "2_2") (pintype "passive"))
      (node (ref "D5") (pin "2") (pinfunction "A_2") (pintype "bidirectional"))
      (node (ref "L5") (pin "2") (pinfunction "2_2") (pintype "passive"))
      (node (ref "Q3") (pin "3") (pinfunction "D_3") (pintype "bidirectional"))
    )
    (net (code "37") (name "Net-(EPD_C1-Pad2)") (class "Default")
      (node (ref "EPD_C1") (pin "2") (pinfunction "2_2") (pintype "passive"))
      (node (ref "J1") (pin "5") (pinfunction "5_5") (pintype "bidirectional"))
    )
    (net (code "38") (name "Net-(EPD_C2-Pad2)") (class "Default")
      (node (ref "EPD_C2") (pin "2") (pinfunction "2_2") (pintype "passive"))
      (node (ref "J1") (pin "4") (pinfunction "4_4") (pintype "bidirectional"))
    )
    (net (code "39") (name "Net-(EPD_C6-Pad2)") (class "Default")
      (node (ref "EPD_C6") (pin "2") (pinfunction "2_2") (pintype "passive"))
      (node (ref "J1") (pin "18") (pinfunction "18_18") (pintype "bidirectional"))
    )
    (net (code "40") (name "Net-(EPD_C7-Pad2)") (class "Default")
      (node (ref "EPD_C7") (pin "2") (pinfunction "2_2") (pintype "passive"))
      (node (ref "J1") (pin "19") (pinfunction "19_19") (pintype "bidirectional"))
    )
    (net (code "41") (name "Net-(EPD_C8-Pad2)") (class "Default")
      (node (ref "EPD_C8") (pin "2") (pinfunction "2_2") (pintype "passive"))
      (node (ref "J1") (pin "20") (pinfunction "20_20") (pintype "bidirectional"))
    )
    (net (code "42") (name "Net-(EPD_C10-Pad2)") (class "Default")
      (node (ref "EPD_C10") (pin "2") (pinfunction "2_2") (pintype "passive"))
      (node (ref "J1") (pin "22") (pinfunction "22_22") (pintype "bidirectional"))
    )
    (net (code "43") (name "Net-(EPD_C12-Pad2)") (class "Default")
      (node (ref "EPD_C12") (pin "2") (pinfunction "2_2") (pintype "passive"))
      (node (ref "J1") (pin "24") (pinfunction "24_24") (pintype "bidirectional"))
    )
    (net (code "44") (name "Net-(IC1-TS{slash}MR)") (class "Default")
      (node (ref "IC1") (pin "D1") (pinfunction "TS/MR_D1") (pintype "bidirectional"))
      (node (ref "R9") (pin "2") (pinfunction "2_2") (pintype "bidirectional"))
    )
    (net (code "45") (name "Net-(IC2-REG)") (class "Default")
      (node (ref "C32") (pin "2") (pinfunction "2_2") (pintype "passive"))
      (node (ref "IC2") (pin "A2") (pinfunction "REG_A2") (pintype "bidirectional"))
    )
    (net (code "46") (name "Net-(IC3-SDO)") (class "Default")
      (node (ref "IC3") (pin "1") (pinfunction "SDO_1") (pintype "bidirectional"))
      (node (ref "R3") (pin "2") (pinfunction "2_2") (pintype "bidirectional"))
    )
    (net (code "47") (name "Net-(IC9-SCL)") (class "Default")
      (node (ref "IC9") (pin "D1") (pinfunction "SCL_D1") (pintype "bidirectional"))
      (node (ref "R4") (pin "2") (pinfunction "2_2") (pintype "bidirectional"))
    )
    (net (code "48") (name "Net-(IC9-SDA)") (class "Default")
      (node (ref "IC9") (pin "E1") (pinfunction "SDA_E1") (pintype "bidirectional"))
      (node (ref "R2") (pin "2") (pinfunction "2_2") (pintype "bidirectional"))
    )
    (net (code "49") (name "Net-(J4-CC1)") (class "Default")
      (node (ref "J4") (pin "A5") (pinfunction "CC1_A5") (pintype "bidirectional"))
      (node (ref "R1_USB") (pin "2") (pinfunction "2_2") (pintype "bidirectional"))
    )
    (net (code "50") (name "Net-(J4-CC2)") (class "Default")
      (node (ref "J4") (pin "B5") (pinfunction "CC2_B5") (pintype "bidirectional"))
      (node (ref "R2_USB") (pin "1") (pinfunction "1_1") (pintype "bidirectional"))
    )
    (net (code "51") (name "Net-(L2-Pad2)") (class "Default")
      (node (ref "L2") (pin "2") (pinfunction "2_2") (pintype "passive"))
      (node (ref "L3") (pin "1") (pinfunction "1_1") (pintype "passive"))
    )
    (net (code "52") (name "Net-(R1_EP_DR-Pad1)") (class "Default")
      (node (ref "R1_EP_DR") (pin "1") (pinfunction "1_1") (pintype "bidirectional"))
      (node (ref "R_TYPE_SEL") (pin "2") (pinfunction "2_2") (pintype "bidirectional"))
      (node (ref "SJ1") (pin "2") (pinfunction "2_2") (pintype "passive"))
    )
    (net (code "53") (name "Net-(U1-ANT)") (class "Default")
      (node (ref "C3") (pin "1") (pinfunction "1_1") (pintype "passive"))
      (node (ref "L1") (pin "1") (pinfunction "1_1") (pintype "passive"))
      (node (ref "U1") (pin "P$H23") (pinfunction "ANT_P$H23") (pintype "bidirectional"))
    )
    (net (code "54") (name "Net-(U1-DCC)") (class "Default")
      (node (ref "L2") (pin "1") (pinfunction "1_1") (pintype "passive"))
      (node (ref "U1") (pin "P$B3") (pinfunction "DCC_P$B3") (pintype "output"))
    )
    (net (code "55") (name "Net-(U1-DEC1)") (class "Default")
      (node (ref "C5") (pin "1") (pinfunction "1_1") (pintype "passive"))
      (node (ref "U1") (pin "P$C1") (pinfunction "DEC1_P$C1") (pintype "power_in"))
    )
    (net (code "56") (name "Net-(U1-DEC2)") (class "Default")
      (node (ref "C13") (pin "1") (pinfunction "1_1") (pintype "passive"))
      (node (ref "U1") (pin "P$A18") (pinfunction "DEC2_P$A18") (pintype "bidirectional"))
    )
    (net (code "57") (name "Net-(U1-DEC3)") (class "Default")
      (node (ref "C11") (pin "1") (pinfunction "1_1") (pintype "passive"))
      (node (ref "U1") (pin "P$D23") (pinfunction "DEC3_P$D23") (pintype "bidirectional"))
    )
    (net (code "58") (name "Net-(U1-DEC3V3)") (class "Default")
      (node (ref "C20") (pin "1") (pinfunction "1_1") (pintype "passive"))
      (node (ref "U1") (pin "P$AC5") (pinfunction "DEC3V3_P$AC5") (pintype "bidirectional"))
    )
    (net (code "59") (name "Net-(U1-DEC4)") (class "Default")
      (node (ref "C10") (pin "1") (pinfunction "1_1") (pintype "passive"))
      (node (ref "C15") (pin "1") (pinfunction "1_1") (pintype "passive"))
      (node (ref "C16") (pin "1") (pinfunction "1_1") (pintype "passive"))
      (node (ref "L3") (pin "2") (pinfunction "2_2") (pintype "passive"))
      (node (ref "U1") (pin "P$B5") (pinfunction "DEC4_P$B5") (pintype "power_in"))
      (node (ref "U1") (pin "P$E24") (pinfunction "DEC6_P$E24") (pintype "bidirectional"))
    )
    (net (code "60") (name "Net-(U1-DEC5)") (class "Default")
      (node (ref "C9") (pin "1") (pinfunction "1_1") (pintype "passive"))
      (node (ref "U1") (pin "P$N24") (pinfunction "DEC5_P$N24") (pintype "bidirectional"))
    )
    (net (code "61") (name "Net-(U1-P0.00{slash}XL1)") (class "Default")
      (node (ref "C17") (pin "2") (pinfunction "2_2") (pintype "passive"))
      (node (ref "U1") (pin "P$D2") (pinfunction "P0.00/XL1_P$D2") (pintype "bidirectional"))
      (node (ref "X2") (pin "2") (pinfunction "2_2") (pintype "passive"))
    )
    (net (code "62") (name "Net-(U1-P0.01{slash}XL2)") (class "Default")
      (node (ref "C18") (pin "1") (pinfunction "1_1") (pintype "passive"))
      (node (ref "U1") (pin "P$F2") (pinfunction "P0.01/XL2_P$F2") (pintype "bidirectional"))
      (node (ref "X2") (pin "1") (pinfunction "1_1") (pintype "passive"))
    )
    (net (code "63") (name "Net-(U1-XC1)") (class "Default")
      (node (ref "C1") (pin "1") (pinfunction "1_1") (pintype "passive"))
      (node (ref "U1") (pin "P$B24") (pinfunction "XC1_P$B24") (pintype "input"))
      (node (ref "X1") (pin "1") (pinfunction "1_1") (pintype "passive"))
    )
    (net (code "64") (name "Net-(U1-XC2)") (class "Default")
      (node (ref "C2") (pin "1") (pinfunction "1_1") (pintype "passive"))
      (node (ref "U1") (pin "P$A23") (pinfunction "XC2_P$A23") (pintype "output"))
      (node (ref "X1") (pin "3") (pinfunction "3_3") (pintype "passive"))
    )
    (net (code "65") (name "OUT") (class "Default")
      (node (ref "IC2") (pin "C3") (pinfunction "OUT-_C3") (pintype "bidirectional"))
    )
    (net (code "66") (name "OUT+") (class "Default")
      (node (ref "IC2") (pin "A3") (pinfunction "OUT+_A3") (pintype "bidirectional"))
      (node (ref "TP_OP") (pin "TP") (pinfunction "TP_TP") (pintype "input"))
    )
    (net (code "67") (name "OUT-") (class "Default")
      (node (ref "TP_ON") (pin "TP") (pinfunction "TP_TP") (pintype "input"))
    )
    (net (code "68") (name "P0.04") (class "Default")
      (node (ref "U1") (pin "P$J1") (pinfunction "P0.04/AIN2_P$J1") (pintype "bidirectional"))
    )
    (net (code "69") (name "P0.09") (class "Default")
      (node (ref "U1") (pin "P$L24") (pinfunction "P0.09/NFC1_P$L24") (pintype "bidirectional"))
    )
    (net (code "70") (name "P0.13{slash}1.5D") (class "Default")
      (node (ref "C30") (pin "2") (pinfunction "2_2") (pintype "passive"))
      (node (ref "R5") (pin "1") (pinfunction "1_1") (pintype "bidirectional"))
      (node (ref "SW_UP") (pin "2") (pinfunction "2_2") (pintype "passive"))
    )
    (net (code "71") (name "P0.13{slash}2.6C") (class "Default")
      (node (ref "U1") (pin "P$AD8") (pinfunction "P0.13_P$AD8") (pintype "bidirectional"))
    )
    (net (code "72") (name "P0.14{slash}1.5D") (class "Default")
      (node (ref "SW_ENT") (pin "2") (pinfunction "2_2") (pintype "passive"))
    )
    (net (code "73") (name "P0.14{slash}2.7C") (class "Default")
      (node (ref "U1") (pin "P$AC9") (pinfunction "P0.14_P$AC9") (pintype "bidirectional"))
    )
    (net (code "74") (name "P0.19") (class "Default")
      (node (ref "U1") (pin "P$AC15") (pinfunction "P0.19_P$AC15") (pintype "bidirectional"))
    )
    (net (code "75") (name "P0.20") (class "Default")
      (node (ref "U1") (pin "P$AD16") (pinfunction "P0.20_P$AD16") (pintype "bidirectional"))
    )
    (net (code "76") (name "P0.21") (class "Default")
      (node (ref "U1") (pin "P$AC17") (pinfunction "P0.21_P$AC17") (pintype "bidirectional"))
    )
    (net (code "77") (name "P0.22") (class "Default")
      (node (ref "U1") (pin "P$AD18") (pinfunction "P0.22_P$AD18") (pintype "bidirectional"))
    )
    (net (code "78") (name "P0.23") (class "Default")
      (node (ref "U1") (pin "P$AC19") (pinfunction "P0.23_P$AC19") (pintype "bidirectional"))
    )
    (net (code "79") (name "P0.24") (class "Default")
      (node (ref "U1") (pin "P$AD20") (pinfunction "P0.24_P$AD20") (pintype "bidirectional"))
    )
    (net (code "80") (name "P0.25") (class "Default")
      (node (ref "U1") (pin "P$AC21") (pinfunction "P0.25_P$AC21") (pintype "bidirectional"))
    )
    (net (code "81") (name "P0.26") (class "Default")
      (node (ref "U1") (pin "P$G1") (pinfunction "P0.26_P$G1") (pintype "bidirectional"))
    )
    (net (code "82") (name "P0.27") (class "Default")
      (node (ref "U1") (pin "P$H2") (pinfunction "P0.27_P$H2") (pintype "bidirectional"))
    )
    (net (code "83") (name "P0.28") (class "Default")
      (node (ref "U1") (pin "P$B11") (pinfunction "P0.28/AIN4_P$B11") (pintype "bidirectional"))
    )
    (net (code "84") (name "P0.29") (class "Default")
      (node (ref "U1") (pin "P$A10") (pinfunction "P0.29/AIN5_P$A10") (pintype "bidirectional"))
    )
    (net (code "85") (name "P0.30") (class "Default")
      (node (ref "U1") (pin "P$B9") (pinfunction "P0.30/AIN6_P$B9") (pintype "bidirectional"))
    )
    (net (code "86") (name "P0.31") (class "Default")
      (node (ref "U1") (pin "P$A8") (pinfunction "P0.31/AIN7_P$A8") (pintype "bidirectional"))
    )
    (net (code "87") (name "P1.01{slash}1.6C") (class "Default")
      (node (ref "DMG2305UX-7") (pin "1") (pinfunction "G_1") (pintype "bidirectional"))
      (node (ref "R_PWR_EPD") (pin "1") (pinfunction "1_1") (pintype "bidirectional"))
    )
    (net (code "88") (name "P1.01{slash}2.4B") (class "Default")
      (node (ref "U1") (pin "P$Y23") (pinfunction "P1.01_P$Y23") (pintype "bidirectional"))
    )
    (net (code "89") (name "P1.02{slash}1.6C") (class "Default")
      (node (ref "SW_DN") (pin "2") (pinfunction "2_2") (pintype "passive"))
    )
    (net (code "90") (name "P1.02{slash}2.8C") (class "Default")
      (node (ref "U1") (pin "P$W24") (pinfunction "P1.02_P$W24") (pintype "bidirectional"))
    )
    (net (code "91") (name "P1.03") (class "Default")
      (node (ref "U1") (pin "P$V23") (pinfunction "P1.03_P$V23") (pintype "bidirectional"))
    )
    (net (code "92") (name "P1.04") (class "Default")
      (node (ref "U1") (pin "P$U24") (pinfunction "P1.04_P$U24") (pintype "bidirectional"))
    )
    (net (code "93") (name "P1.05") (class "Default")
      (node (ref "U1") (pin "P$T23") (pinfunction "P1.05_P$T23") (pintype "bidirectional"))
    )
    (net (code "94") (name "P1.06") (class "Default")
      (node (ref "U1") (pin "P$R24") (pinfunction "P1.06_P$R24") (pintype "bidirectional"))
    )
    (net (code "95") (name "P1.07") (class "Default")
      (node (ref "U1") (pin "P$P23") (pinfunction "P1.07_P$P23") (pintype "bidirectional"))
    )
    (net (code "96") (name "P1.09") (class "Default")
      (node (ref "U1") (pin "P$R1") (pinfunction "P1.09_P$R1") (pintype "bidirectional"))
    )
    (net (code "97") (name "P1.10") (class "Default")
      (node (ref "U1") (pin "P$A20") (pinfunction "P1.10_P$A20") (pintype "bidirectional"))
    )
    (net (code "98") (name "P1.11") (class "Default")
      (node (ref "U1") (pin "P$B19") (pinfunction "P1.11_P$B19") (pintype "bidirectional"))
    )
    (net (code "99") (name "P1.12") (class "Default")
      (node (ref "U1") (pin "P$B17") (pinfunction "P1.12_P$B17") (pintype "bidirectional"))
    )
    (net (code "100") (name "P1.13") (class "Default")
      (node (ref "U1") (pin "P$A16") (pinfunction "P1.13_P$A16") (pintype "bidirectional"))
    )
    (net (code "101") (name "P1.14") (class "Default")
      (node (ref "U1") (pin "P$B15") (pinfunction "P1.14_P$B15") (pintype "bidirectional"))
    )
    (net (code "102") (name "P1.15") (class "Default")
      (node (ref "U1") (pin "P$A14") (pinfunction "P1.15_P$A14") (pintype "bidirectional"))
    )
    (net (code "103") (name "PMIC_INT") (class "Default")
      (node (ref "IC1") (pin "A1") (pinfunction "~{INT}_A1") (pintype "bidirectional"))
      (node (ref "U1") (pin "P$T2") (pinfunction "P0.11_P$T2") (pintype "bidirectional"))
    )
    (net (code "104") (name "PREVGH") (class "Default")
      (node (ref "D5") (pin "1") (pinfunction "K_1") (pintype "bidirectional"))
      (node (ref "EPD_C9") (pin "2") (pinfunction "2_2") (pintype "passive"))
      (node (ref "J1") (pin "21") (pinfunction "21_21") (pintype "bidirectional"))
    )
    (net (code "105") (name "PREVGL") (class "Default")
      (node (ref "D2") (pin "2") (pinfunction "A_2") (pintype "bidirectional"))
      (node (ref "EPD_C11") (pin "2") (pinfunction "2_2") (pintype "passive"))
      (node (ref "J1") (pin "23") (pinfunction "23_23") (pintype "bidirectional"))
    )
    (net (code "106") (name "RESE") (class "Default")
      (node (ref "J1") (pin "3") (pinfunction "3_3") (pintype "bidirectional"))
      (node (ref "Q3") (pin "2") (pinfunction "S_2") (pintype "bidirectional"))
      (node (ref "R1_EP_DR") (pin "2") (pinfunction "2_2") (pintype "bidirectional"))
    )
    (net (code "107") (name "RESET") (class "Default")
      (node (ref "J2") (pin "6") (pinfunction "6_6") (pintype "bidirectional"))
      (node (ref "TP_RESET") (pin "TP") (pinfunction "TP_TP") (pintype "input"))
      (node (ref "U1") (pin "P$AC13") (pinfunction "P0.18/RESET_P$AC13") (pintype "bidirectional"))
    )
    (net (code "108") (name "SCK{slash}1.5B") (class "Default")
      (node (ref "J1") (pin "13") (pinfunction "13_13") (pintype "bidirectional"))
    )
    (net (code "109") (name "SCK{slash}2.2D") (class "Default")
      (node (ref "U1") (pin "P$A12") (pinfunction "P0.02/AIN0_P$A12") (pintype "bidirectional"))
    )
    (net (code "110") (name "SCL{slash}1.4C") (class "Default")
      (node (ref "IC2") (pin "C1") (pinfunction "SCL_C1") (pintype "bidirectional"))
      (node (ref "U3") (pin "7") (pinfunction "SCL_7") (pintype "input"))
    )
    (net (code "111") (name "SCL{slash}2.4C") (class "Default")
      (node (ref "IC1") (pin "B1") (pinfunction "SCL_B1") (pintype "bidirectional"))
      (node (ref "IC3") (pin "12") (pinfunction "SCX_12") (pintype "bidirectional"))
      (node (ref "R17") (pin "2") (pinfunction "2_2") (pintype "bidirectional"))
      (node (ref "R4") (pin "1") (pinfunction "1_1") (pintype "bidirectional"))
      (node (ref "TP_SCL") (pin "TP") (pinfunction "TP_TP") (pintype "input"))
      (node (ref "U1") (pin "P$M2") (pinfunction "P0.07_P$M2") (pintype "bidirectional"))
    )
    (net (code "112") (name "SDA{slash}1.4C") (class "Default")
      (node (ref "IC2") (pin "B2") (pinfunction "SDA_B2") (pintype "bidirectional"))
      (node (ref "U3") (pin "8") (pinfunction "SDA_8") (pintype "bidirectional"))
    )
    (net (code "113") (name "SDA{slash}2.4C") (class "Default")
      (node (ref "IC1") (pin "C1") (pinfunction "SDA_C1") (pintype "bidirectional"))
      (node (ref "IC3") (pin "2") (pinfunction "SDX_2") (pintype "bidirectional"))
      (node (ref "R18") (pin "2") (pinfunction "2_2") (pintype "bidirectional"))
      (node (ref "R2") (pin "1") (pinfunction "1_1") (pintype "bidirectional"))
      (node (ref "TP_SDA") (pin "TP") (pinfunction "TP_TP") (pintype "input"))
      (node (ref "U1") (pin "P$L1") (pinfunction "P0.06_P$L1") (pintype "bidirectional"))
    )
    (net (code "114") (name "SWDCLK") (class "Default")
      (node (ref "J2") (pin "4") (pinfunction "4_4") (pintype "bidirectional"))
      (node (ref "TP_SWDCLK") (pin "TP") (pinfunction "TP_TP") (pintype "input"))
      (node (ref "U1") (pin "P$AA24") (pinfunction "SWDCLK_P$AA24") (pintype "input"))
    )
    (net (code "115") (name "SWDIO") (class "Default")
      (node (ref "J2") (pin "2") (pinfunction "2_2") (pintype "bidirectional"))
      (node (ref "TP_SWDIO") (pin "TP") (pinfunction "TP_TP") (pintype "input"))
      (node (ref "U1") (pin "P$AC24") (pinfunction "SWDIO_P$AC24") (pintype "bidirectional"))
    )
    (net (code "116") (name "SWO") (class "Default")
      (node (ref "TP_SWO") (pin "TP") (pinfunction "TP_TP") (pintype "input"))
      (node (ref "U1") (pin "P$AD22") (pinfunction "P1.00_P$AD22") (pintype "bidirectional"))
    )
    (net (code "117") (name "VBAT{slash}1.2A") (class "Default")
      (node (ref "C27") (pin "2") (pinfunction "2_2") (pintype "passive"))
      (node (ref "TP_VBAT") (pin "TP") (pinfunction "TP_TP") (pintype "input"))
      (node (ref "U3") (pin "2") (pinfunction "CELL_2") (pintype "power_in"))
      (node (ref "U3") (pin "3") (pinfunction "VDD_3") (pintype "power_in"))
    )
    (net (code "118") (name "VBAT{slash}2.5C") (class "Default")
      (node (ref "C37") (pin "2") (pinfunction "2_2") (pintype "passive"))
      (node (ref "IC1") (pin "C2") (pinfunction "BAT_C2") (pintype "bidirectional"))
    )
    (net (code "119") (name "VBUS{slash}1.5D") (class "Default")
      (node (ref "C42") (pin "1") (pinfunction "1_1") (pintype "passive"))
      (node (ref "C43") (pin "1") (pinfunction "1_1") (pintype "passive"))
      (node (ref "D3") (pin "5") (pinfunction "VBUS_5") (pintype "bidirectional"))
      (node (ref "J4") (pin "A4_B9") (pinfunction "VBUS_A4_B9") (pintype "power_in"))
      (node (ref "J4") (pin "A9_B4") (pinfunction "VBUS_A9_B4") (pintype "power_in"))
    )
    (net (code "120") (name "VBUS{slash}2.6D") (class "Default")
      (node (ref "C21") (pin "1") (pinfunction "1_1") (pintype "passive"))
      (node (ref "C38") (pin "2") (pinfunction "2_2") (pintype "passive"))
      (node (ref "IC1") (pin "A2") (pinfunction "IN_A2") (pintype "bidirectional"))
      (node (ref "U1") (pin "P$AD2") (pinfunction "VBUS_P$AD2") (pintype "power_in"))
    )
    (net (code "121") (name "VREG") (class "Default")
      (node (ref "C23") (pin "1") (pinfunction "1_1") (pintype "passive"))
      (node (ref "C24") (pin "1") (pinfunction "1_1") (pintype "passive"))
      (node (ref "C39") (pin "1") (pinfunction "1_1") (pintype "passive"))
      (node (ref "IC1") (pin "B2") (pinfunction "SYS_B2") (pintype "bidirectional"))
      (node (ref "IC9") (pin "A1") (pinfunction "EN_A1") (pintype "bidirectional"))
      (node (ref "IC9") (pin "A2") (pinfunction "VIN_1_A2") (pintype "bidirectional"))
      (node (ref "IC9") (pin "A3") (pinfunction "VIN_2_A3") (pintype "bidirectional"))
      (node (ref "TP_VREG") (pin "TP") (pinfunction "TP_TP") (pintype "input"))
    )
    (net (code "122") (name "unconnected-(ANT1-NC-Pad2)") (class "Default")
      (node (ref "ANT1") (pin "2") (pinfunction "NC_2") (pintype "no_connect"))
    )
    (net (code "123") (name "unconnected-(IC3-ASCL-Pad11)") (class "Default")
      (node (ref "IC3") (pin "11") (pinfunction "ASCL_11") (pintype "bidirectional"))
    )
    (net (code "124") (name "unconnected-(IC3-ASDA-Pad4)") (class "Default")
      (node (ref "IC3") (pin "4") (pinfunction "ASDA_4") (pintype "bidirectional"))
    )
    (net (code "125") (name "unconnected-(J1-Pad1)") (class "Default")
      (node (ref "J1") (pin "1") (pinfunction "1_1") (pintype "bidirectional"))
    )
    (net (code "126") (name "unconnected-(J1-Pad6)") (class "Default")
      (node (ref "J1") (pin "6") (pinfunction "6_6") (pintype "bidirectional"))
    )
    (net (code "127") (name "unconnected-(J1-Pad7)") (class "Default")
      (node (ref "J1") (pin "7") (pinfunction "7_7") (pintype "bidirectional"))
    )
    (net (code "128") (name "unconnected-(J4-SBU1-PadA8)") (class "Default")
      (node (ref "J4") (pin "A8") (pinfunction "SBU1_A8") (pintype "bidirectional"))
    )
    (net (code "129") (name "unconnected-(J4-SBU2-PadB8)") (class "Default")
      (node (ref "J4") (pin "B8") (pinfunction "SBU2_B8") (pintype "bidirectional"))
    )
    (net (code "130") (name "unconnected-(U1-DCCH-PadP$AB2)") (class "Default")
      (node (ref "U1") (pin "P$AB2") (pinfunction "DCCH_P$AB2") (pintype "bidirectional"))
    )
  )
)
